# gydrodrive_sto.net
KiCad netlist of a schematic drawn in Altium Designer
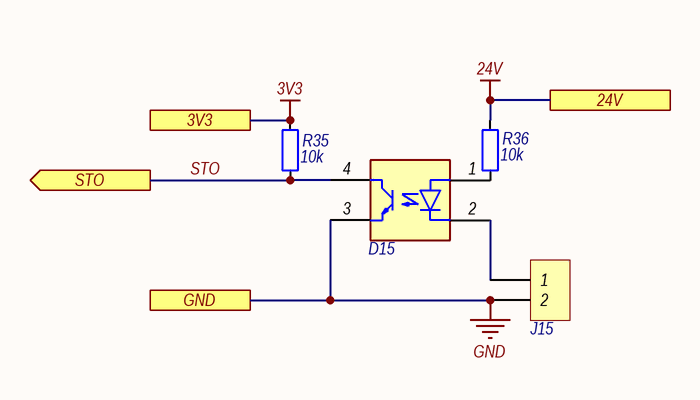
[diagram p0: gydrodrive_sto.SchDoc]

(export (version "E")
  (design (tool "Eeschema 10.0.6"))
  (components
    (comp (ref "D15")
      (value "LTV-817S")
      (footprint "DIP-4-SMD")
      (description "Оптопара транзисторная одноканальная")
      (libsource (lib "StdLib") (part "LTV-817"))
    )
    (comp (ref "J15")
      (value "DG142V-5.08-02P")
      (footprint "DG142V-5.08-02P")
      (description "Клеммник 2-контактный, шаг 5.08 мм")
      (libsource (lib "StdLib") (part "PIN1x2"))
    )
    (comp (ref "R35")
      (value "RES_0805")
      (footprint "RESC2012-0805M")
      (description "Рез-р, корпус 0805")
      (fields
        (field (name "RESISTANCE") "10k")
        (field (name "PART NUMBER") "RESC_0805")
        (field (name "TOLERANCE") "5%")
      )
      (libsource (lib "StdLib") (part "RES"))
    )
    (comp (ref "R36")
      (value "RES_0805")
      (footprint "RESC2012-0805M")
      (description "Рез-р, корпус 0805")
      (fields
        (field (name "RESISTANCE") "10k")
        (field (name "PART NUMBER") "RESC_0805")
        (field (name "TOLERANCE") "5%")
      )
      (libsource (lib "StdLib") (part "RES"))
    )
  )
  (nets
    (net (code "1") (name "/STO") (class "Default")
      (node (ref "D15") (pin "4") (pinfunction "A_4") (pintype "passive"))
      (node (ref "R35") (pin "1") (pinfunction "1_1") (pintype "passive"))
    )
    (net (code "2") (name "3V3") (class "Default")
      (node (ref "R35") (pin "2") (pinfunction "2_2") (pintype "passive"))
    )
    (net (code "3") (name "24V") (class "Default")
      (node (ref "R36") (pin "2") (pinfunction "2_2") (pintype "passive"))
    )
    (net (code "4") (name "GND") (class "Default")
      (node (ref "D15") (pin "3") (pinfunction "C_3") (pintype "passive"))
      (node (ref "J15") (pin "2") (pinfunction "2_2") (pintype "passive"))
    )
    (net (code "5") (name "Net-(D15-E)") (class "Default")
      (node (ref "D15") (pin "2") (pinfunction "E_2") (pintype "passive"))
      (node (ref "J15") (pin "1") (pinfunction "1_1") (pintype "passive"))
    )
    (net (code "6") (name "Net-(D15-K)") (class "Default")
      (node (ref "D15") (pin "1") (pinfunction "K_1") (pintype "passive"))
      (node (ref "R36") (pin "1") (pinfunction "1_1") (pintype "passive"))
    )
  )
)
